# MCU.net
KiCad netlist of a schematic drawn in Altium Designer
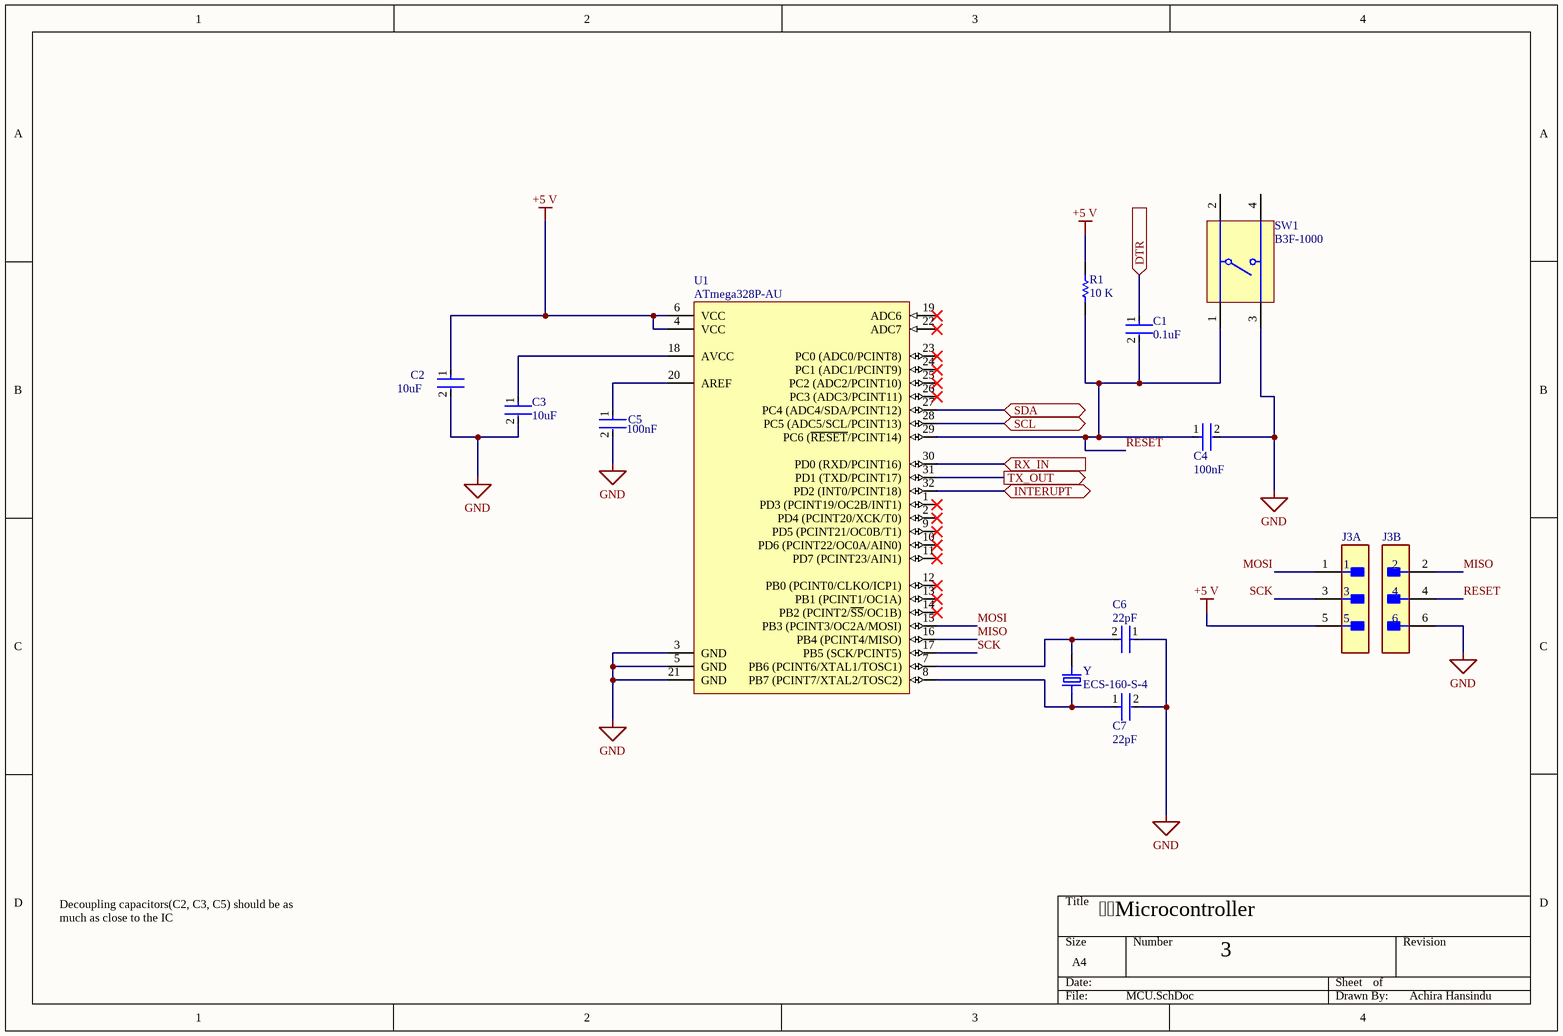
[diagram p0: MCU.SchDoc]

(export (version "E")
  (design (tool "Eeschema 10.0.6"))
  (components
    (comp (ref "C1")
      (value "GRM31M1X1H104JA01L")
      (footprint "FP-GRM31M-0_15-IPC_A")
      (fields
        (field (name "VOLTAGE") "50V")
        (field (name "TOLERANCE") "5%")
        (field (name "CAPACITANCE") "0.1uF")
      )
      (libsource (lib "Altium Content Vault") (part "b4654b650e69147ec39a6b967a45e02"))
    )
    (comp (ref "C2")
      (value "C1206C106K4PACTU")
      (footprint "FP-C1206C106K4PACTU-MFG")
      (description "CAP CER 10UF 16V X5R 1206")
      (fields
        (field (name "TOLERANCE") "10%")
        (field (name "VOLTAGE") "16V")
        (field (name "CAPACITANCE") "10uF")
      )
      (libsource (lib "Altium Content Vault") (part "e9c51b7dd13d4faca003ae77663ab08"))
    )
    (comp (ref "C3")
      (value "C1206C106K4PACTU")
      (footprint "FP-C1206C106K4PACTU-MFG")
      (description "CAP CER 10UF 16V X5R 1206")
      (fields
        (field (name "TOLERANCE") "10%")
        (field (name "VOLTAGE") "16V")
        (field (name "CAPACITANCE") "10uF")
      )
      (libsource (lib "Altium Content Vault") (part "e9c51b7dd13d4faca003ae77663ab08"))
    )
    (comp (ref "C4")
      (value "CL05B104KO5NNWC")
      (footprint "FP-CL640-IPC_C")
      (description "Cap Ceramic 100nF 16V X7R ±10% SMD 0402 +125°C Paper T/R")
      (fields (field (name "TOLERANCE") "10%") (field (name "CAPACITANCE") "100nF"))
      (libsource (lib "Altium Content Vault") (part "b4654b650e69147ec39a6b967a45e02"))
    )
    (comp (ref "C5")
      (value "CL05B104KO5NNWC")
      (footprint "FP-CL640-IPC_C")
      (description "Cap Ceramic 100nF 16V X7R ±10% SMD 0402 +125°C Paper T/R")
      (fields (field (name "TOLERANCE") "10%") (field (name "CAPACITANCE") "100nF"))
      (libsource (lib "Altium Content Vault") (part "b4654b650e69147ec39a6b967a45e02"))
    )
    (comp (ref "C6")
      (value "22pF")
      (footprint "FP-GRM31A-0_2-e0_3_0_8-IPC_B")
      (description "Chip Multilayer Ceramic Capacitors for General Purpose, 1206, 22pF, U2J, -750ppm/°C, 5%, 2kV")
      (fields (field (name "TOLERANCE") "5%") (field (name "Comment") "GRM31A7U3D220JW31D"))
      (libsource (lib "Altium Content Vault") (part "02cd4be3c70576c341d710602a673aa"))
    )
    (comp (ref "C7")
      (value "GRM31A7U3D220JW31D")
      (footprint "FP-GRM31A-0_2-e0_3_0_8-IPC_B")
      (description "Chip Multilayer Ceramic Capacitors for General Purpose, 1206, 22pF, U2J, -750ppm/°C, 5%, 2kV")
      (fields (field (name "TOLERANCE") "5%") (field (name "CAPACITANCE") "22pF"))
      (libsource (lib "Altium Content Vault") (part "02cd4be3c70576c341d710602a673aa"))
    )
    (comp (ref "J3")
      (value "90131-0763")
      (footprint "FP-90131-0763-MFG")
      (description "90131-0763 Conn Unshrouded Header HDR 6 POS 2.54mm Solder ST Top Entry Thru-Hole C-Grid III™ Tray")
      (libsource (lib "") (part "2654a11fb13586ecb194516b1c997bc_1"))
    )
    (comp (ref "R1")
      (value "10 K")
      (footprint "RESC3216X70X50LL20T25")
      (fields (field (name "MANUFACTURER") "Panasonic") (field (name "PART NUMBER") "ERA8AEB103V"))
      (libsource (lib "Altium Content Vault") (part "RES"))
    )
    (comp (ref "SW1")
      (value "B3F-1000")
      (footprint "OMRON-B3F-1000-4_V")
      (description "Tactile Switch, SPST-NO, 0.05 A, 24 V, -25 to 70 degC, 4-Pin THD, RoHS, Bulk")
      (fields (field (name "MANUFACTURER") "Omron Electronic Components"))
      (libsource (lib "Achira Hansindu") (part "SW-SPST-4_A"))
    )
    (comp (ref "U1")
      (value "ATmega328P-AU")
      (footprint "32A_M")
      (libsource (lib "Altium Content Vault") (part "MC-8B-ATM48-SQ32"))
    )
    (comp (ref "Y")
      (value "ECS-160-S-4")
      (footprint "XTAL_ECS-160-20-4X")
      (description "16MHz Â±30ppm Crystal Series 40 Ohms HC-49/US")
      (fields (field (name "MF") "ECS Inc."))
      (libsource (lib "ECS-160-S-4") (part "ECS-160-S-4"))
    )
  )
  (nets
    (net (code "1") (name "+5 V") (class "Default")
      (node (ref "C2") (pin "1") (pinfunction "1_1") (pintype "passive"))
      (node (ref "J3") (pin "5") (pinfunction "5_5") (pintype "passive"))
      (node (ref "R1") (pin "2") (pinfunction "2_2") (pintype "passive"))
      (node (ref "U1") (pin "4") (pinfunction "VCC_4") (pintype "power_in"))
      (node (ref "U1") (pin "6") (pinfunction "VCC_6") (pintype "power_in"))
    )
    (net (code "2") (name "/DTR") (class "Default")
      (node (ref "C1") (pin "1") (pinfunction "1_1") (pintype "passive"))
    )
    (net (code "3") (name "/INTERUPT") (class "Default")
      (node (ref "U1") (pin "32") (pinfunction "PD2_(INT0/PCINT18)_32") (pintype "bidirectional"))
    )
    (net (code "4") (name "/MISO") (class "Default")
      (node (ref "J3") (pin "2") (pinfunction "2_2") (pintype "passive"))
      (node (ref "U1") (pin "16") (pinfunction "PB4_(PCINT4/MISO)_16") (pintype "bidirectional"))
    )
    (net (code "5") (name "/MOSI") (class "Default")
      (node (ref "J3") (pin "1") (pinfunction "1_1") (pintype "passive"))
      (node (ref "U1") (pin "15") (pinfunction "PB3_(PCINT3/OC2A/MOSI)_15") (pintype "bidirectional"))
    )
    (net (code "6") (name "/RESET") (class "Default")
      (node (ref "C1") (pin "2") (pinfunction "2_2") (pintype "passive"))
      (node (ref "C4") (pin "1") (pinfunction "1_1") (pintype "passive"))
      (node (ref "J3") (pin "4") (pinfunction "4_4") (pintype "passive"))
      (node (ref "R1") (pin "1") (pinfunction "1_1") (pintype "passive"))
      (node (ref "SW1") (pin "1") (pinfunction "1_1") (pintype "passive"))
      (node (ref "U1") (pin "29") (pinfunction "PC6_(~{RESET}/PCINT14)_29") (pintype "bidirectional"))
    )
    (net (code "7") (name "/RX_IN") (class "Default")
      (node (ref "U1") (pin "30") (pinfunction "PD0_(RXD/PCINT16)_30") (pintype "bidirectional"))
    )
    (net (code "8") (name "/SCK") (class "Default")
      (node (ref "J3") (pin "3") (pinfunction "3_3") (pintype "passive"))
      (node (ref "U1") (pin "17") (pinfunction "PB5_(SCK/PCINT5)_17") (pintype "bidirectional"))
    )
    (net (code "9") (name "/SCL") (class "Default")
      (node (ref "U1") (pin "28") (pinfunction "PC5_(ADC5/SCL/PCINT13)_28") (pintype "bidirectional"))
    )
    (net (code "10") (name "/SDA") (class "Default")
      (node (ref "U1") (pin "27") (pinfunction "PC4_(ADC4/SDA/PCINT12)_27") (pintype "bidirectional"))
    )
    (net (code "11") (name "/TX_OUT") (class "Default")
      (node (ref "U1") (pin "31") (pinfunction "PD1_(TXD/PCINT17)_31") (pintype "bidirectional"))
    )
    (net (code "12") (name "GND") (class "Default")
      (node (ref "C2") (pin "2") (pinfunction "2_2") (pintype "passive"))
      (node (ref "C3") (pin "2") (pinfunction "2_2") (pintype "passive"))
      (node (ref "C4") (pin "2") (pinfunction "2_2") (pintype "passive"))
      (node (ref "C5") (pin "2") (pinfunction "2_2") (pintype "passive"))
      (node (ref "C6") (pin "1") (pinfunction "1_1") (pintype "passive"))
      (node (ref "C7") (pin "2") (pinfunction "2_2") (pintype "passive"))
      (node (ref "J3") (pin "6") (pinfunction "6_6") (pintype "passive"))
      (node (ref "SW1") (pin "3") (pinfunction "3_3") (pintype "passive"))
      (node (ref "U1") (pin "21") (pinfunction "GND_21") (pintype "power_in"))
      (node (ref "U1") (pin "3") (pinfunction "GND_3") (pintype "power_in"))
      (node (ref "U1") (pin "5") (pinfunction "GND_5") (pintype "power_in"))
    )
    (net (code "13") (name "Net-(U1-AREF)") (class "Default")
      (node (ref "C5") (pin "1") (pinfunction "1_1") (pintype "passive"))
      (node (ref "U1") (pin "20") (pinfunction "AREF_20") (pintype "passive"))
    )
    (net (code "14") (name "Net-(U1-AVCC)") (class "Default")
      (node (ref "C3") (pin "1") (pinfunction "1_1") (pintype "passive"))
      (node (ref "U1") (pin "18") (pinfunction "AVCC_18") (pintype "power_in"))
    )
    (net (code "15") (name "Net-(U1-PB6_(PCINT6{slash}XTAL1{slash}TOSC1))") (class "Default")
      (node (ref "C6") (pin "2") (pinfunction "2_2") (pintype "passive"))
      (node (ref "U1") (pin "7") (pinfunction "PB6_(PCINT6/XTAL1/TOSC1)_7") (pintype "bidirectional"))
      (node (ref "Y") (pin "2") (pinfunction "2_2") (pintype "passive"))
    )
    (net (code "16") (name "Net-(U1-PB7_(PCINT7{slash}XTAL2{slash}TOSC2))") (class "Default")
      (node (ref "C7") (pin "1") (pinfunction "1_1") (pintype "passive"))
      (node (ref "U1") (pin "8") (pinfunction "PB7_(PCINT7/XTAL2/TOSC2)_8") (pintype "bidirectional"))
      (node (ref "Y") (pin "1") (pinfunction "1_1") (pintype "passive"))
    )
    (net (code "17") (name "unconnected-(SW1-Pad2)") (class "Default")
      (node (ref "SW1") (pin "2") (pinfunction "2_2") (pintype "passive"))
    )
    (net (code "18") (name "unconnected-(SW1-Pad4)") (class "Default")
      (node (ref "SW1") (pin "4") (pinfunction "4_4") (pintype "passive"))
    )
    (net (code "19") (name "unconnected-(U1-ADC6-Pad19)") (class "Default")
      (node (ref "U1") (pin "19") (pinfunction "ADC6_19") (pintype "input+no_connect"))
    )
    (net (code "20") (name "unconnected-(U1-ADC7-Pad22)") (class "Default")
      (node (ref "U1") (pin "22") (pinfunction "ADC7_22") (pintype "input+no_connect"))
    )
    (net (code "21") (name "unconnected-(U1-PB0_(PCINT0{slash}CLKO{slash}ICP1)-Pad12)") (class "Default")
      (node (ref "U1") (pin "12") (pinfunction "PB0_(PCINT0/CLKO/ICP1)_12") (pintype "bidirectional+no_connect"))
    )
    (net (code "22") (name "unconnected-(U1-PB1_(PCINT1{slash}OC1A)-Pad13)") (class "Default")
      (node (ref "U1") (pin "13") (pinfunction "PB1_(PCINT1/OC1A)_13") (pintype "bidirectional+no_connect"))
    )
    (net (code "23") (name "unconnected-(U1-PB2_(PCINT2{slash}~{SS}{slash}OC1B)-Pad14)") (class "Default")
      (node (ref "U1") (pin "14") (pinfunction "PB2_(PCINT2/~{SS}/OC1B)_14") (pintype "bidirectional+no_connect"))
    )
    (net (code "24") (name "unconnected-(U1-PC0_(ADC0{slash}PCINT8)-Pad23)") (class "Default")
      (node (ref "U1") (pin "23") (pinfunction "PC0_(ADC0/PCINT8)_23") (pintype "bidirectional+no_connect"))
    )
    (net (code "25") (name "unconnected-(U1-PC1_(ADC1{slash}PCINT9)-Pad24)") (class "Default")
      (node (ref "U1") (pin "24") (pinfunction "PC1_(ADC1/PCINT9)_24") (pintype "bidirectional+no_connect"))
    )
    (net (code "26") (name "unconnected-(U1-PC2_(ADC2{slash}PCINT10)-Pad25)") (class "Default")
      (node (ref "U1") (pin "25") (pinfunction "PC2_(ADC2/PCINT10)_25") (pintype "bidirectional+no_connect"))
    )
    (net (code "27") (name "unconnected-(U1-PC3_(ADC3{slash}PCINT11)-Pad26)") (class "Default")
      (node (ref "U1") (pin "26") (pinfunction "PC3_(ADC3/PCINT11)_26") (pintype "bidirectional+no_connect"))
    )
    (net (code "28") (name "unconnected-(U1-PD3_(PCINT19{slash}OC2B{slash}INT1)-Pad1)") (class "Default")
      (node (ref "U1") (pin "1") (pinfunction "PD3_(PCINT19/OC2B/INT1)_1") (pintype "bidirectional+no_connect"))
    )
    (net (code "29") (name "unconnected-(U1-PD4_(PCINT20{slash}XCK{slash}T0)-Pad2)") (class "Default")
      (node (ref "U1") (pin "2") (pinfunction "PD4_(PCINT20/XCK/T0)_2") (pintype "bidirectional+no_connect"))
    )
    (net (code "30") (name "unconnected-(U1-PD5_(PCINT21{slash}OC0B{slash}T1)-Pad9)") (class "Default")
      (node (ref "U1") (pin "9") (pinfunction "PD5_(PCINT21/OC0B/T1)_9") (pintype "bidirectional+no_connect"))
    )
    (net (code "31") (name "unconnected-(U1-PD6_(PCINT22{slash}OC0A{slash}AIN0)-Pad10)") (class "Default")
      (node (ref "U1") (pin "10") (pinfunction "PD6_(PCINT22/OC0A/AIN0)_10") (pintype "bidirectional+no_connect"))
    )
    (net (code "32") (name "unconnected-(U1-PD7_(PCINT23{slash}AIN1)-Pad11)") (class "Default")
      (node (ref "U1") (pin "11") (pinfunction "PD7_(PCINT23/AIN1)_11") (pintype "bidirectional+no_connect"))
    )
  )
)
